# IICLCDKeyPad.net
KiCad netlist of a schematic drawn in EAGLE
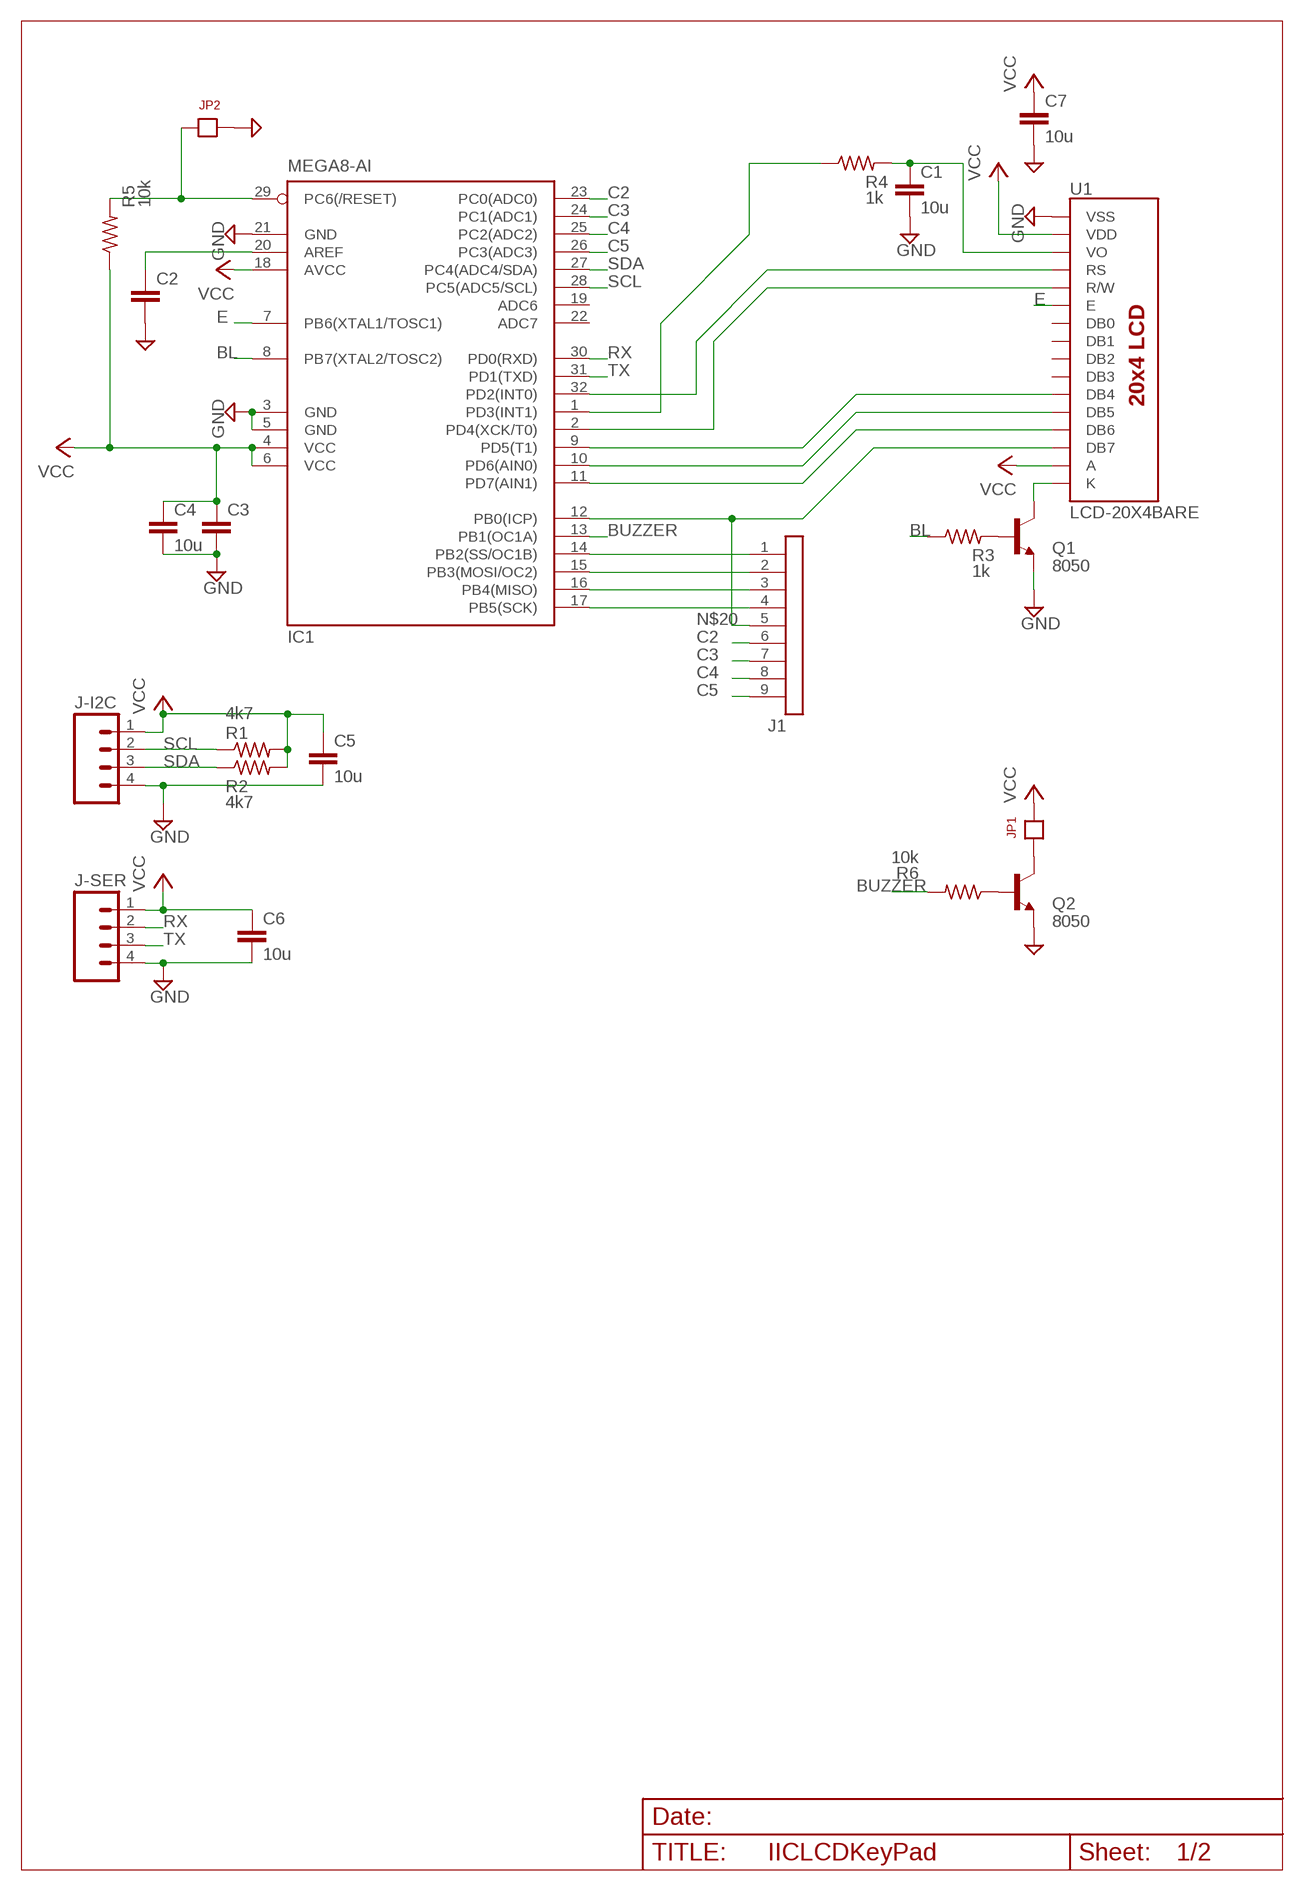
[diagram p0: schematic, sheet 1]

(export (version "E")
  (design (tool "Eeschema 10.0.6"))
  (components
    (comp (ref "C1")
      (value "10u")
      (footprint "eagle-import:0805")
      (libsource (lib "eagle-import") (part "CAP0805"))
    )
    (comp (ref "C2")
      (value "CAP0603-CAP")
      (footprint "eagle-import:0603-CAP")
      (libsource (lib "eagle-import") (part "CAP0603-CAP"))
    )
    (comp (ref "C3")
      (value "CAP0603-CAP")
      (footprint "eagle-import:0603-CAP")
      (libsource (lib "eagle-import") (part "CAP0603-CAP"))
    )
    (comp (ref "C4")
      (value "10u")
      (footprint "eagle-import:0805")
      (libsource (lib "eagle-import") (part "CAP0805"))
    )
    (comp (ref "C5")
      (value "10u")
      (footprint "eagle-import:0805")
      (libsource (lib "eagle-import") (part "CAP0805"))
    )
    (comp (ref "C6")
      (value "10u")
      (footprint "eagle-import:0805")
      (libsource (lib "eagle-import") (part "CAP0805"))
    )
    (comp (ref "C7")
      (value "10u")
      (footprint "eagle-import:0805")
      (libsource (lib "eagle-import") (part "CAP0805"))
    )
    (comp (ref "IC1")
      (value "MEGA8-AI")
      (footprint "eagle-import:TQFP32-08")
      (fields
        (field (name "MPN") "ATMEGA8-16AU")
        (field (name "MPN_1") "ATMEGA8-16AU")
        (field (name "OC_FARNELL") "9171371")
        (field (name "OC_NEWARK") "73M8863")
      )
      (libsource (lib "eagle-import") (part "MEGA8-AI"))
    )
    (comp (ref "J-I2C")
      (value "MO4POL")
      (footprint "eagle-import:MOLEX-4")
      (libsource (lib "eagle-import") (part "MO4POL"))
    )
    (comp (ref "J-SER")
      (value "MO4POL")
      (footprint "eagle-import:MOLEX-4")
      (libsource (lib "eagle-import") (part "MO4POL"))
    )
    (comp (ref "J1")
      (value "SIL-9")
      (footprint "eagle-import:SIL-9")
      (libsource (lib "eagle-import") (part "SIL-9"))
    )
    (comp (ref "JP1")
      (value "JP1")
      (footprint "eagle-import:JP1")
      (libsource (lib "eagle-import") (part "JP1"))
    )
    (comp (ref "JP2")
      (value "JP1")
      (footprint "eagle-import:JP1")
      (libsource (lib "eagle-import") (part "JP1"))
    )
    (comp (ref "Q1")
      (value "8050")
      (footprint "eagle-import:SOT23-BEC")
      (libsource (lib "eagle-import") (part "BC849SMD"))
    )
    (comp (ref "Q2")
      (value "8050")
      (footprint "eagle-import:SOT23-BEC")
      (libsource (lib "eagle-import") (part "BC849SMD"))
    )
    (comp (ref "R1")
      (value "4k7")
      (footprint "eagle-import:R0603")
      (libsource (lib "eagle-import") (part "R-US_R0603"))
    )
    (comp (ref "R2")
      (value "4k7")
      (footprint "eagle-import:R0603")
      (libsource (lib "eagle-import") (part "R-US_R0603"))
    )
    (comp (ref "R3")
      (value "1k")
      (footprint "eagle-import:R0603")
      (libsource (lib "eagle-import") (part "R-US_R0603"))
    )
    (comp (ref "R4")
      (value "1k")
      (footprint "eagle-import:R0603")
      (libsource (lib "eagle-import") (part "R-US_R0603"))
    )
    (comp (ref "R5")
      (value "10k")
      (footprint "eagle-import:R0603")
      (libsource (lib "eagle-import") (part "R-US_R0603"))
    )
    (comp (ref "R6")
      (value "10k")
      (footprint "eagle-import:R0603")
      (libsource (lib "eagle-import") (part "R-US_R0603"))
    )
    (comp (ref "U1")
      (value "LCD-20X4BARE")
      (footprint "eagle-import:LCD-16X2_BARE")
      (libsource (lib "eagle-import") (part "LCD-20X4BARE"))
    )
  )
  (nets
    (net (code "1") (name "BL") (class "Default")
      (node (ref "IC1") (pin "8") (pinfunction "PB7(XTAL2/TOSC2)_8") (pintype "bidirectional"))
      (node (ref "R3") (pin "1") (pinfunction "1_1") (pintype "passive"))
    )
    (net (code "2") (name "BUZZER") (class "Default")
      (node (ref "IC1") (pin "13") (pinfunction "PB1(OC1A)_13") (pintype "bidirectional"))
      (node (ref "R6") (pin "2") (pinfunction "2_2") (pintype "passive"))
    )
    (net (code "3") (name "C2") (class "Default")
      (node (ref "IC1") (pin "23") (pinfunction "PC0(ADC0)_23") (pintype "bidirectional"))
      (node (ref "J1") (pin "6") (pinfunction "6_6") (pintype "bidirectional"))
    )
    (net (code "4") (name "C3") (class "Default")
      (node (ref "IC1") (pin "24") (pinfunction "PC1(ADC1)_24") (pintype "bidirectional"))
      (node (ref "J1") (pin "7") (pinfunction "7_7") (pintype "bidirectional"))
    )
    (net (code "5") (name "C4") (class "Default")
      (node (ref "IC1") (pin "25") (pinfunction "PC2(ADC2)_25") (pintype "bidirectional"))
      (node (ref "J1") (pin "8") (pinfunction "8_8") (pintype "bidirectional"))
    )
    (net (code "6") (name "C5") (class "Default")
      (node (ref "IC1") (pin "26") (pinfunction "PC3(ADC3)_26") (pintype "bidirectional"))
      (node (ref "J1") (pin "9") (pinfunction "9_9") (pintype "bidirectional"))
    )
    (net (code "7") (name "E") (class "Default")
      (node (ref "IC1") (pin "7") (pinfunction "PB6(XTAL1/TOSC1)_7") (pintype "bidirectional"))
      (node (ref "U1") (pin "6") (pinfunction "E_6") (pintype "input"))
    )
    (net (code "8") (name "GND") (class "Default")
      (node (ref "C1") (pin "2") (pinfunction "2_2") (pintype "passive"))
      (node (ref "C2") (pin "2") (pinfunction "2_2") (pintype "passive"))
      (node (ref "C3") (pin "2") (pinfunction "2_2") (pintype "passive"))
      (node (ref "C4") (pin "2") (pinfunction "2_2") (pintype "passive"))
      (node (ref "C5") (pin "2") (pinfunction "2_2") (pintype "passive"))
      (node (ref "C6") (pin "2") (pinfunction "2_2") (pintype "passive"))
      (node (ref "C7") (pin "2") (pinfunction "2_2") (pintype "passive"))
      (node (ref "IC1") (pin "21") (pinfunction "GND_21") (pintype "power_in"))
      (node (ref "IC1") (pin "3") (pinfunction "GND_3") (pintype "power_in"))
      (node (ref "IC1") (pin "5") (pinfunction "GND_5") (pintype "power_in"))
      (node (ref "J-I2C") (pin "4") (pinfunction "4_4") (pintype "passive"))
      (node (ref "J-SER") (pin "4") (pinfunction "4_4") (pintype "passive"))
      (node (ref "JP2") (pin "2") (pinfunction "2_2") (pintype "bidirectional"))
      (node (ref "Q1") (pin "E") (pinfunction "E_E") (pintype "passive"))
      (node (ref "Q2") (pin "E") (pinfunction "E_E") (pintype "passive"))
      (node (ref "U1") (pin "1") (pinfunction "VSS_1") (pintype "power_in"))
    )
    (net (code "9") (name "N$20") (class "Default")
      (node (ref "IC1") (pin "12") (pinfunction "PB0(ICP)_12") (pintype "bidirectional"))
      (node (ref "J1") (pin "5") (pinfunction "5_5") (pintype "bidirectional"))
      (node (ref "U1") (pin "14") (pinfunction "DB7_14") (pintype "bidirectional"))
    )
    (net (code "10") (name "Net-(IC1-AREF)") (class "Default")
      (node (ref "C2") (pin "1") (pinfunction "1_1") (pintype "passive"))
      (node (ref "IC1") (pin "20") (pinfunction "AREF_20") (pintype "passive"))
    )
    (net (code "11") (name "Net-(IC1-PB2(SS{slash}OC1B))") (class "Default")
      (node (ref "IC1") (pin "14") (pinfunction "PB2(SS/OC1B)_14") (pintype "bidirectional"))
      (node (ref "J1") (pin "1") (pinfunction "1_1") (pintype "bidirectional"))
    )
    (net (code "12") (name "Net-(IC1-PB3(MOSI{slash}OC2))") (class "Default")
      (node (ref "IC1") (pin "15") (pinfunction "PB3(MOSI/OC2)_15") (pintype "bidirectional"))
      (node (ref "J1") (pin "2") (pinfunction "2_2") (pintype "bidirectional"))
    )
    (net (code "13") (name "Net-(IC1-PB4(MISO))") (class "Default")
      (node (ref "IC1") (pin "16") (pinfunction "PB4(MISO)_16") (pintype "bidirectional"))
      (node (ref "J1") (pin "3") (pinfunction "3_3") (pintype "bidirectional"))
    )
    (net (code "14") (name "Net-(IC1-PB5(SCK))") (class "Default")
      (node (ref "IC1") (pin "17") (pinfunction "PB5(SCK)_17") (pintype "bidirectional"))
      (node (ref "J1") (pin "4") (pinfunction "4_4") (pintype "bidirectional"))
    )
    (net (code "15") (name "Net-(IC1-PC6({slash}RESET))") (class "Default")
      (node (ref "IC1") (pin "29") (pinfunction "PC6(/RESET)_29") (pintype "bidirectional"))
      (node (ref "JP2") (pin "1") (pinfunction "1_1") (pintype "bidirectional"))
      (node (ref "R5") (pin "2") (pinfunction "2_2") (pintype "passive"))
    )
    (net (code "16") (name "Net-(IC1-PD2(INT0))") (class "Default")
      (node (ref "IC1") (pin "32") (pinfunction "PD2(INT0)_32") (pintype "bidirectional"))
      (node (ref "U1") (pin "4") (pinfunction "RS_4") (pintype "input"))
    )
    (net (code "17") (name "Net-(IC1-PD3(INT1))") (class "Default")
      (node (ref "IC1") (pin "1") (pinfunction "PD3(INT1)_1") (pintype "bidirectional"))
      (node (ref "R4") (pin "1") (pinfunction "1_1") (pintype "passive"))
    )
    (net (code "18") (name "Net-(IC1-PD4(XCK{slash}T0))") (class "Default")
      (node (ref "IC1") (pin "2") (pinfunction "PD4(XCK/T0)_2") (pintype "bidirectional"))
      (node (ref "U1") (pin "5") (pinfunction "R/W_5") (pintype "input"))
    )
    (net (code "19") (name "Net-(IC1-PD5(T1))") (class "Default")
      (node (ref "IC1") (pin "9") (pinfunction "PD5(T1)_9") (pintype "bidirectional"))
      (node (ref "U1") (pin "11") (pinfunction "DB4_11") (pintype "bidirectional"))
    )
    (net (code "20") (name "Net-(IC1-PD6(AIN0))") (class "Default")
      (node (ref "IC1") (pin "10") (pinfunction "PD6(AIN0)_10") (pintype "bidirectional"))
      (node (ref "U1") (pin "12") (pinfunction "DB5_12") (pintype "bidirectional"))
    )
    (net (code "21") (name "Net-(IC1-PD7(AIN1))") (class "Default")
      (node (ref "IC1") (pin "11") (pinfunction "PD7(AIN1)_11") (pintype "bidirectional"))
      (node (ref "U1") (pin "13") (pinfunction "DB6_13") (pintype "bidirectional"))
    )
    (net (code "22") (name "Net-(JP1-Pad1)") (class "Default")
      (node (ref "JP1") (pin "1") (pinfunction "1_1") (pintype "bidirectional"))
      (node (ref "Q2") (pin "C") (pinfunction "C_C") (pintype "passive"))
    )
    (net (code "23") (name "Net-(Q1-PadB)") (class "Default")
      (node (ref "Q1") (pin "B") (pinfunction "B_B") (pintype "passive"))
      (node (ref "R3") (pin "2") (pinfunction "2_2") (pintype "passive"))
    )
    (net (code "24") (name "Net-(Q2-PadB)") (class "Default")
      (node (ref "Q2") (pin "B") (pinfunction "B_B") (pintype "passive"))
      (node (ref "R6") (pin "1") (pinfunction "1_1") (pintype "passive"))
    )
    (net (code "25") (name "Net-(U1-K)") (class "Default")
      (node (ref "Q1") (pin "C") (pinfunction "C_C") (pintype "passive"))
      (node (ref "U1") (pin "16") (pinfunction "K_16") (pintype "power_in"))
    )
    (net (code "26") (name "Net-(U1-VO)") (class "Default")
      (node (ref "C1") (pin "1") (pinfunction "1_1") (pintype "passive"))
      (node (ref "R4") (pin "2") (pinfunction "2_2") (pintype "passive"))
      (node (ref "U1") (pin "3") (pinfunction "VO_3") (pintype "bidirectional"))
    )
    (net (code "27") (name "RX") (class "Default")
      (node (ref "IC1") (pin "30") (pinfunction "PD0(RXD)_30") (pintype "bidirectional"))
      (node (ref "J-SER") (pin "2") (pinfunction "2_2") (pintype "passive"))
    )
    (net (code "28") (name "SCL") (class "Default")
      (node (ref "IC1") (pin "28") (pinfunction "PC5(ADC5/SCL)_28") (pintype "bidirectional"))
      (node (ref "J-I2C") (pin "2") (pinfunction "2_2") (pintype "passive"))
      (node (ref "R1") (pin "1") (pinfunction "1_1") (pintype "passive"))
    )
    (net (code "29") (name "SDA") (class "Default")
      (node (ref "IC1") (pin "27") (pinfunction "PC4(ADC4/SDA)_27") (pintype "bidirectional"))
      (node (ref "J-I2C") (pin "3") (pinfunction "3_3") (pintype "passive"))
      (node (ref "R2") (pin "1") (pinfunction "1_1") (pintype "passive"))
    )
    (net (code "30") (name "TX") (class "Default")
      (node (ref "IC1") (pin "31") (pinfunction "PD1(TXD)_31") (pintype "bidirectional"))
      (node (ref "J-SER") (pin "3") (pinfunction "3_3") (pintype "passive"))
    )
    (net (code "31") (name "VCC") (class "Default")
      (node (ref "C3") (pin "1") (pinfunction "1_1") (pintype "passive"))
      (node (ref "C4") (pin "1") (pinfunction "1_1") (pintype "passive"))
      (node (ref "C5") (pin "1") (pinfunction "1_1") (pintype "passive"))
      (node (ref "C6") (pin "1") (pinfunction "1_1") (pintype "passive"))
      (node (ref "C7") (pin "1") (pinfunction "1_1") (pintype "passive"))
      (node (ref "IC1") (pin "18") (pinfunction "AVCC_18") (pintype "power_in"))
      (node (ref "IC1") (pin "4") (pinfunction "VCC_4") (pintype "power_in"))
      (node (ref "IC1") (pin "6") (pinfunction "VCC_6") (pintype "power_in"))
      (node (ref "J-I2C") (pin "1") (pinfunction "1_1") (pintype "passive"))
      (node (ref "J-SER") (pin "1") (pinfunction "1_1") (pintype "passive"))
      (node (ref "JP1") (pin "2") (pinfunction "2_2") (pintype "bidirectional"))
      (node (ref "R1") (pin "2") (pinfunction "2_2") (pintype "passive"))
      (node (ref "R2") (pin "2") (pinfunction "2_2") (pintype "passive"))
      (node (ref "R5") (pin "1") (pinfunction "1_1") (pintype "passive"))
      (node (ref "U1") (pin "15") (pinfunction "A_15") (pintype "power_in"))
      (node (ref "U1") (pin "2") (pinfunction "VDD_2") (pintype "power_in"))
    )
    (net (code "32") (name "unconnected-(IC1-ADC6-Pad19)") (class "Default")
      (node (ref "IC1") (pin "19") (pinfunction "ADC6_19") (pintype "bidirectional"))
    )
    (net (code "33") (name "unconnected-(IC1-ADC7-Pad22)") (class "Default")
      (node (ref "IC1") (pin "22") (pinfunction "ADC7_22") (pintype "bidirectional"))
    )
    (net (code "34") (name "unconnected-(U1-DB0-Pad7)") (class "Default")
      (node (ref "U1") (pin "7") (pinfunction "DB0_7") (pintype "bidirectional"))
    )
    (net (code "35") (name "unconnected-(U1-DB1-Pad8)") (class "Default")
      (node (ref "U1") (pin "8") (pinfunction "DB1_8") (pintype "bidirectional"))
    )
    (net (code "36") (name "unconnected-(U1-DB2-Pad9)") (class "Default")
      (node (ref "U1") (pin "9") (pinfunction "DB2_9") (pintype "bidirectional"))
    )
    (net (code "37") (name "unconnected-(U1-DB3-Pad10)") (class "Default")
      (node (ref "U1") (pin "10") (pinfunction "DB3_10") (pintype "bidirectional"))
    )
  )
)
